# IQDownconverterWaveyRadar.net
KiCad netlist of a schematic drawn in Altium Designer
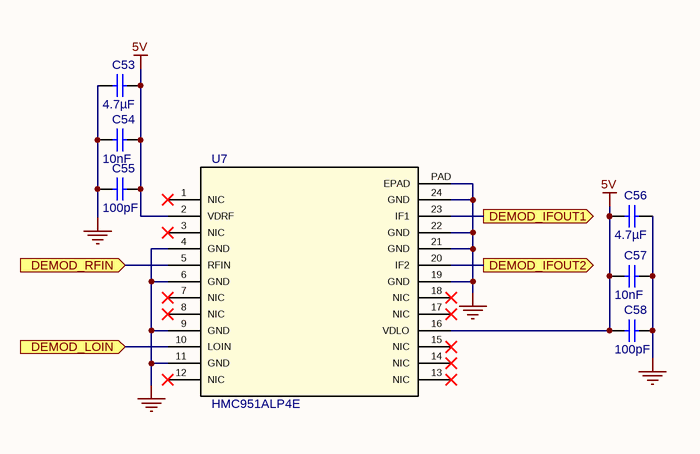
[diagram p0: IQDownconverterWaveyRadar.SchDoc]

(export (version "E")
  (design (tool "Eeschema 10.0.6"))
  (components
    (comp (ref "C53")
      (value "4.7µF")
      (footprint "CAPC0603(1608)100_L")
      (description "Chip Capacitor, 4.7µF +/-20%, 10V, 0603, Thickness 1 mm")
      (fields (field (name "TOLERANCE") "10%") (field (name "Comment") "Capacitor 4.7µF +/-20% 10V 0603"))
      (libsource (lib "University of South Florida") (part "CAP-NP-2"))
    )
    (comp (ref "C54")
      (value "10nF")
      (footprint "CAPC0402(1005)60_L")
      (description "Chip Capacitor, 10nF +/-20%, 50V, 0402, Thickness 0.6 mm")
      (fields (field (name "TOLERANCE") "5%") (field (name "Comment") "Capacitor 10nF +/-20% 50V 0402"))
      (libsource (lib "University of South Florida") (part "CAP-NP-2"))
    )
    (comp (ref "C55")
      (value "100pF")
      (footprint "CAPC1005X56X25LL10T15")
      (fields (field (name "Comment") "04023A101JAT2A"))
      (libsource (lib "University of South Florida") (part "CAP-NP-2"))
    )
    (comp (ref "C56")
      (value "4.7µF")
      (footprint "CAPC0603(1608)100_L")
      (description "Chip Capacitor, 4.7µF +/-20%, 10V, 0603, Thickness 1 mm")
      (fields (field (name "TOLERANCE") "10%") (field (name "Comment") "Capacitor 4.7µF +/-20% 10V 0603"))
      (libsource (lib "University of South Florida") (part "CAP-NP-2"))
    )
    (comp (ref "C57")
      (value "10nF")
      (footprint "CAPC0402(1005)60_L")
      (description "Chip Capacitor, 10nF +/-20%, 50V, 0402, Thickness 0.6 mm")
      (fields (field (name "TOLERANCE") "5%") (field (name "Comment") "Capacitor 10nF +/-20% 50V 0402"))
      (libsource (lib "University of South Florida") (part "CAP-NP-2"))
    )
    (comp (ref "C58")
      (value "100pF")
      (footprint "CAPC1005X56X25LL10T15")
      (fields (field (name "Comment") "04023A101JAT2A"))
      (libsource (lib "University of South Florida") (part "CAP-NP-2"))
    )
    (comp (ref "U7")
      (value "HMC951ALP4E")
      (footprint "HCP_24_3")
      (description "5.6  GHz to 8.6 GHz, GaAs, MMIC, I/Q Downconverter")
      (fields (field (name "COPYRIGHT") "Copyright (C) 2018 Accelerated Designs. All rights reserved"))
      (libsource (lib "University of South Florida") (part "HMC951ALP4E"))
    )
  )
  (nets
    (net (code "1") (name "/DEMOD_IFOUT1") (class "Default")
      (node (ref "U7") (pin "23") (pinfunction "IF1_23") (pintype "passive"))
    )
    (net (code "2") (name "/DEMOD_IFOUT2") (class "Default")
      (node (ref "U7") (pin "20") (pinfunction "IF2_20") (pintype "passive"))
    )
    (net (code "3") (name "/DEMOD_LOIN") (class "Default")
      (node (ref "U7") (pin "10") (pinfunction "LOIN_10") (pintype "passive"))
    )
    (net (code "4") (name "/DEMOD_RFIN") (class "Default")
      (node (ref "U7") (pin "5") (pinfunction "RFIN_5") (pintype "passive"))
    )
    (net (code "5") (name "5V") (class "Default")
      (node (ref "C53") (pin "2") (pinfunction "2_2") (pintype "passive"))
      (node (ref "C54") (pin "2") (pinfunction "2_2") (pintype "passive"))
      (node (ref "C55") (pin "2") (pinfunction "2_2") (pintype "passive"))
      (node (ref "C56") (pin "1") (pinfunction "1_1") (pintype "passive"))
      (node (ref "C57") (pin "1") (pinfunction "1_1") (pintype "passive"))
      (node (ref "C58") (pin "1") (pinfunction "1_1") (pintype "passive"))
      (node (ref "U7") (pin "16") (pinfunction "VDLO_16") (pintype "power_in"))
      (node (ref "U7") (pin "2") (pinfunction "VDRF_2") (pintype "passive"))
    )
    (net (code "6") (name "GND") (class "Default")
      (node (ref "C53") (pin "1") (pinfunction "1_1") (pintype "passive"))
      (node (ref "C54") (pin "1") (pinfunction "1_1") (pintype "passive"))
      (node (ref "C55") (pin "1") (pinfunction "1_1") (pintype "passive"))
      (node (ref "C56") (pin "2") (pinfunction "2_2") (pintype "passive"))
      (node (ref "C57") (pin "2") (pinfunction "2_2") (pintype "passive"))
      (node (ref "C58") (pin "2") (pinfunction "2_2") (pintype "passive"))
      (node (ref "U7") (pin "11") (pinfunction "GND_11") (pintype "power_in"))
      (node (ref "U7") (pin "19") (pinfunction "GND_19") (pintype "power_in"))
      (node (ref "U7") (pin "21") (pinfunction "GND_21") (pintype "power_in"))
      (node (ref "U7") (pin "22") (pinfunction "GND_22") (pintype "power_in"))
      (node (ref "U7") (pin "24") (pinfunction "GND_24") (pintype "power_in"))
      (node (ref "U7") (pin "4") (pinfunction "GND_4") (pintype "power_in"))
      (node (ref "U7") (pin "6") (pinfunction "GND_6") (pintype "power_in"))
      (node (ref "U7") (pin "9") (pinfunction "GND_9") (pintype "power_in"))
      (node (ref "U7") (pin "PAD") (pinfunction "EPAD_PAD") (pintype "passive"))
    )
    (net (code "7") (name "unconnected-(U7-NIC-Pad1)") (class "Default")
      (node (ref "U7") (pin "1") (pinfunction "NIC_1") (pintype "passive+no_connect"))
    )
    (net (code "8") (name "unconnected-(U7-NIC-Pad3)") (class "Default")
      (node (ref "U7") (pin "3") (pinfunction "NIC_3") (pintype "passive+no_connect"))
    )
    (net (code "9") (name "unconnected-(U7-NIC-Pad7)") (class "Default")
      (node (ref "U7") (pin "7") (pinfunction "NIC_7") (pintype "passive+no_connect"))
    )
    (net (code "10") (name "unconnected-(U7-NIC-Pad8)") (class "Default")
      (node (ref "U7") (pin "8") (pinfunction "NIC_8") (pintype "passive+no_connect"))
    )
    (net (code "11") (name "unconnected-(U7-NIC-Pad12)") (class "Default")
      (node (ref "U7") (pin "12") (pinfunction "NIC_12") (pintype "passive+no_connect"))
    )
    (net (code "12") (name "unconnected-(U7-NIC-Pad13)") (class "Default")
      (node (ref "U7") (pin "13") (pinfunction "NIC_13") (pintype "passive+no_connect"))
    )
    (net (code "13") (name "unconnected-(U7-NIC-Pad14)") (class "Default")
      (node (ref "U7") (pin "14") (pinfunction "NIC_14") (pintype "passive+no_connect"))
    )
    (net (code "14") (name "unconnected-(U7-NIC-Pad15)") (class "Default")
      (node (ref "U7") (pin "15") (pinfunction "NIC_15") (pintype "passive+no_connect"))
    )
    (net (code "15") (name "unconnected-(U7-NIC-Pad17)") (class "Default")
      (node (ref "U7") (pin "17") (pinfunction "NIC_17") (pintype "passive+no_connect"))
    )
    (net (code "16") (name "unconnected-(U7-NIC-Pad18)") (class "Default")
      (node (ref "U7") (pin "18") (pinfunction "NIC_18") (pintype "passive+no_connect"))
    )
  )
)
